# XInC2_Dev_-_SCH_v2_0_0_20210410.net
KiCad netlist of a schematic drawn in Altium Designer
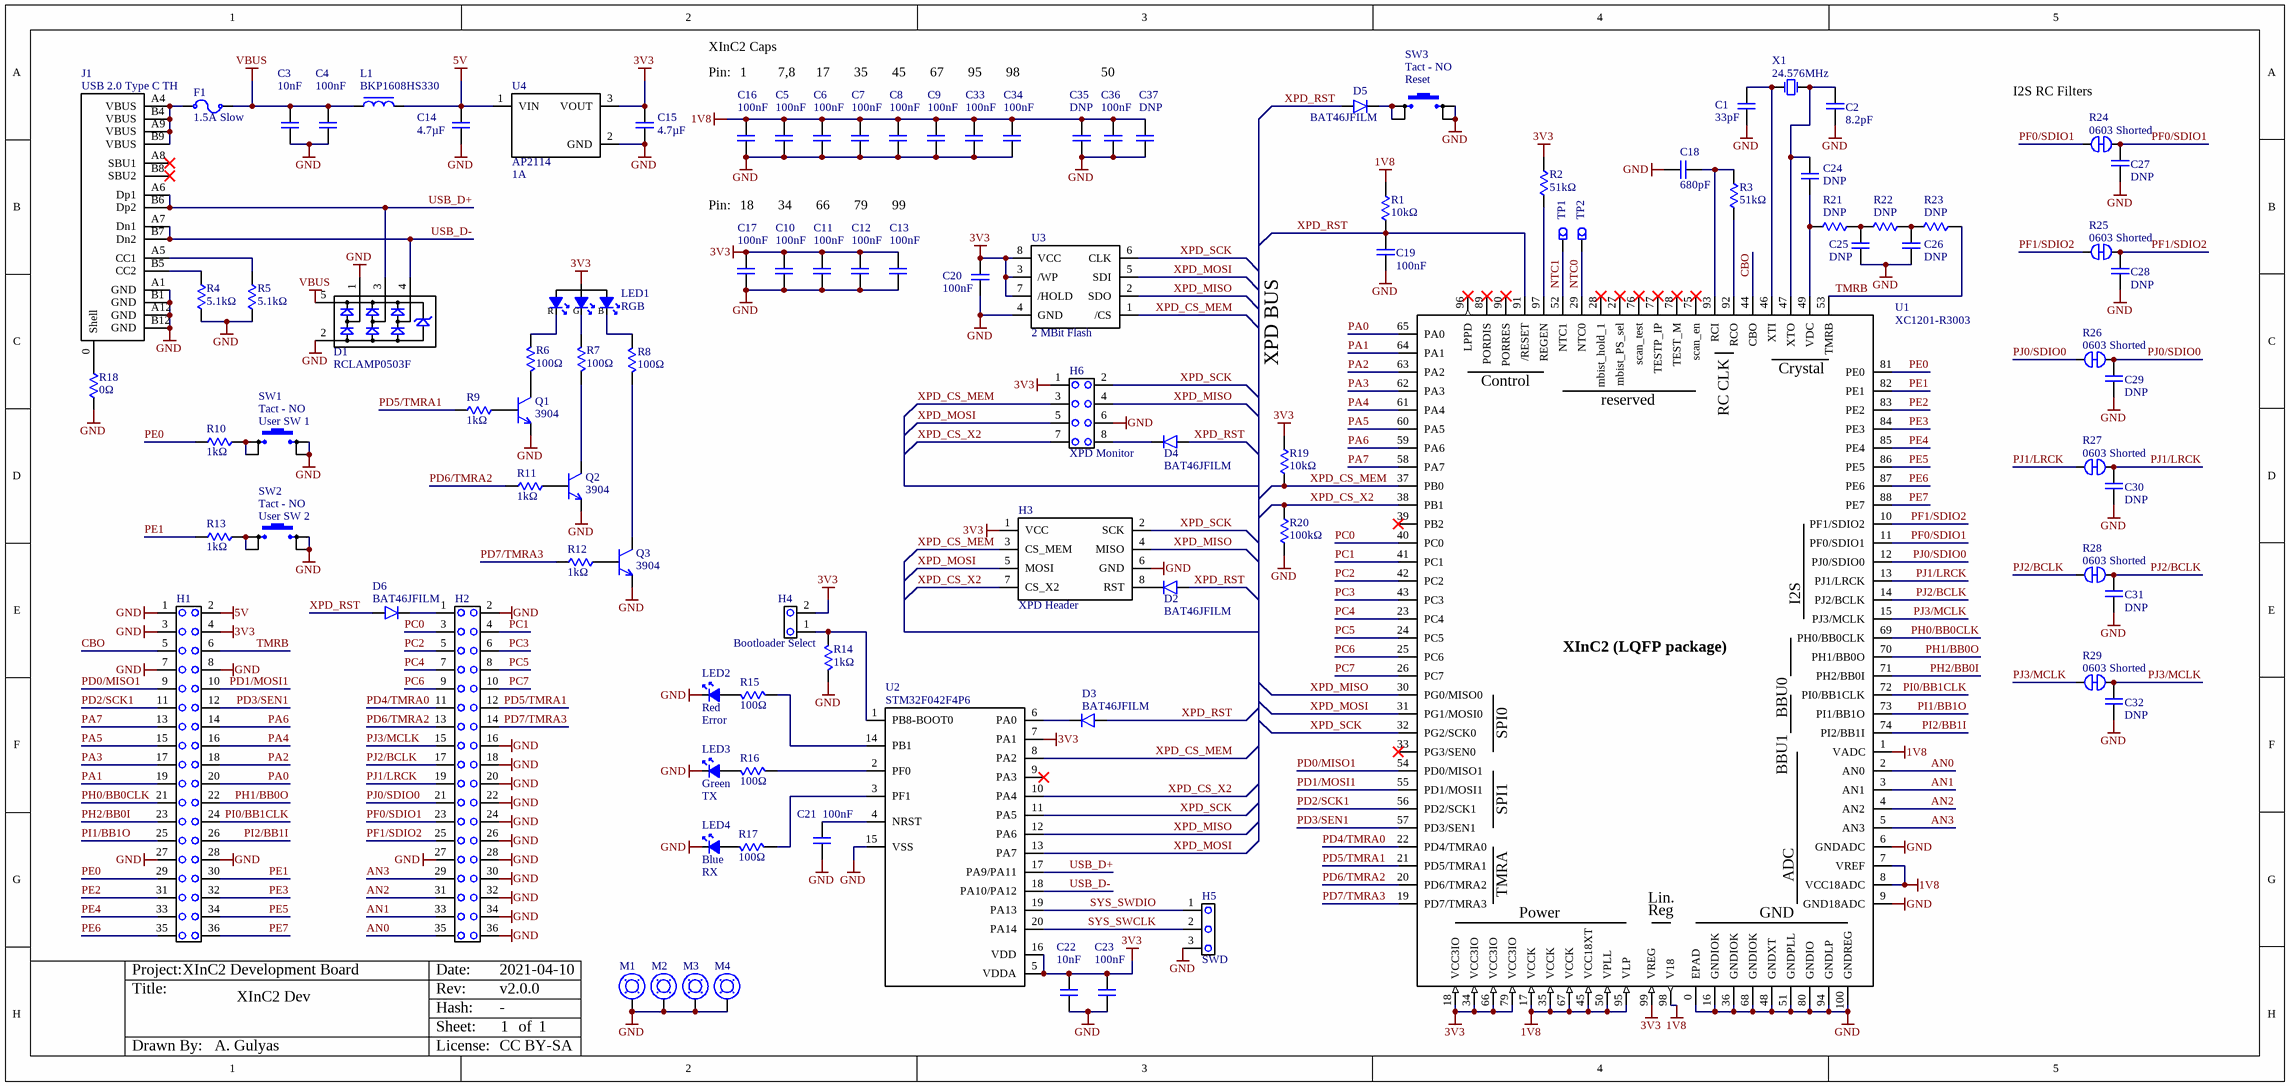
[diagram p0: XInC2 Dev - SCH v2.0.0 20210410.SchDoc]

(export (version "E")
  (design (tool "Eeschema 10.0.6"))
  (components
    (comp (ref "C1")
      (value "33pF")
      (footprint "0603 - C")
      (description "CAP CER 33PF 50V C0G/NPO 0603")
      (fields (field (name "MFG") "Yageo") (field (name "TOLERANCE") "±5%"))
      (libsource (lib "Public Library") (part "C - 0603 - 33pF - 16V_1"))
    )
    (comp (ref "C2")
      (value "8.2pF")
      (footprint "0603 - C")
      (description "CAP CER 8.2PF 50V NPO 0603")
      (fields (field (name "MFG") "Yageo") (field (name "TOLERANCE") "±0.25pF"))
      (libsource (lib "Public Library") (part "C - 0603 - 8.2pF - 50V"))
    )
    (comp (ref "C3")
      (value "10nF")
      (footprint "0603 - C")
      (description "CAP CER 10000PF 50V X7R 0603")
      (fields (field (name "MFG") "Yageo") (field (name "TOLERANCE") "±5%"))
      (libsource (lib "Public Library") (part "C - 0603 - 10nF - 50V"))
    )
    (comp (ref "C4")
      (value "100nF")
      (footprint "0603 - C")
      (description "CAP CER 0.1UF 16V X7R 0603")
      (fields (field (name "MFG") "Yageo") (field (name "TOLERANCE") "±10%"))
      (libsource (lib "Public Library") (part "C - 0603 - 100nF - 16V"))
    )
    (comp (ref "C5")
      (value "100nF")
      (footprint "0603 - C")
      (description "CAP CER 0.1UF 16V X7R 0603")
      (fields (field (name "MFG") "Yageo") (field (name "TOLERANCE") "±10%"))
      (libsource (lib "Public Library") (part "C - 0603 - 100nF - 16V"))
    )
    (comp (ref "C6")
      (value "100nF")
      (footprint "0603 - C")
      (description "CAP CER 0.1UF 16V X7R 0603")
      (fields (field (name "MFG") "Yageo") (field (name "TOLERANCE") "±10%"))
      (libsource (lib "Public Library") (part "C - 0603 - 100nF - 16V"))
    )
    (comp (ref "C7")
      (value "100nF")
      (footprint "0603 - C")
      (description "CAP CER 0.1UF 16V X7R 0603")
      (fields (field (name "MFG") "Yageo") (field (name "TOLERANCE") "±10%"))
      (libsource (lib "Public Library") (part "C - 0603 - 100nF - 16V"))
    )
    (comp (ref "C8")
      (value "100nF")
      (footprint "0603 - C")
      (description "CAP CER 0.1UF 16V X7R 0603")
      (fields (field (name "MFG") "Yageo") (field (name "TOLERANCE") "±10%"))
      (libsource (lib "Public Library") (part "C - 0603 - 100nF - 16V"))
    )
    (comp (ref "C9")
      (value "100nF")
      (footprint "0603 - C")
      (description "CAP CER 0.1UF 16V X7R 0603")
      (fields (field (name "MFG") "Yageo") (field (name "TOLERANCE") "±10%"))
      (libsource (lib "Public Library") (part "C - 0603 - 100nF - 16V"))
    )
    (comp (ref "C10")
      (value "100nF")
      (footprint "0603 - C")
      (description "CAP CER 0.1UF 16V X7R 0603")
      (fields (field (name "MFG") "Yageo") (field (name "TOLERANCE") "±10%"))
      (libsource (lib "Public Library") (part "C - 0603 - 100nF - 16V"))
    )
    (comp (ref "C11")
      (value "100nF")
      (footprint "0603 - C")
      (description "CAP CER 0.1UF 16V X7R 0603")
      (fields (field (name "MFG") "Yageo") (field (name "TOLERANCE") "±10%"))
      (libsource (lib "Public Library") (part "C - 0603 - 100nF - 16V"))
    )
    (comp (ref "C12")
      (value "100nF")
      (footprint "0603 - C")
      (description "CAP CER 0.1UF 16V X7R 0603")
      (fields (field (name "MFG") "Yageo") (field (name "TOLERANCE") "±10%"))
      (libsource (lib "Public Library") (part "C - 0603 - 100nF - 16V"))
    )
    (comp (ref "C13")
      (value "100nF")
      (footprint "0603 - C")
      (description "CAP CER 0.1UF 16V X7R 0603")
      (fields (field (name "MFG") "Yageo") (field (name "TOLERANCE") "±10%"))
      (libsource (lib "Public Library") (part "C - 0603 - 100nF - 16V"))
    )
    (comp (ref "C14")
      (value "4.7µF")
      (footprint "0603 - C")
      (description "CAP CER 4.7UF 10V X5R 0603")
      (fields (field (name "MFG") "Yageo") (field (name "TOLERANCE") "±20%"))
      (libsource (lib "Public Library") (part "C - 0603 - 4.7uF - 10V"))
    )
    (comp (ref "C15")
      (value "4.7µF")
      (footprint "0603 - C")
      (description "CAP CER 4.7UF 10V X5R 0603")
      (fields (field (name "MFG") "Yageo") (field (name "TOLERANCE") "±20%"))
      (libsource (lib "Public Library") (part "C - 0603 - 4.7uF - 10V"))
    )
    (comp (ref "C16")
      (value "100nF")
      (footprint "0603 - C")
      (description "CAP CER 0.1UF 16V X7R 0603")
      (fields (field (name "MFG") "Yageo") (field (name "TOLERANCE") "±10%"))
      (libsource (lib "Public Library") (part "C - 0603 - 100nF - 16V"))
    )
    (comp (ref "C17")
      (value "100nF")
      (footprint "0603 - C")
      (description "CAP CER 0.1UF 16V X7R 0603")
      (fields (field (name "MFG") "Yageo") (field (name "TOLERANCE") "±10%"))
      (libsource (lib "Public Library") (part "C - 0603 - 100nF - 16V"))
    )
    (comp (ref "C18")
      (value "680pF")
      (footprint "0603 - C")
      (description "CAP CER 680PF 50V X7R 0603")
      (fields (field (name "MFG") "Yageo") (field (name "TOLERANCE") "±10%"))
      (libsource (lib "Public Library") (part "C - 0603 - 680pF - 50V"))
    )
    (comp (ref "C19")
      (value "100nF")
      (footprint "0603 - C")
      (description "CAP CER 0.1UF 16V X7R 0603")
      (fields (field (name "MFG") "Yageo") (field (name "TOLERANCE") "±10%"))
      (libsource (lib "Public Library") (part "C - 0603 - 100nF - 16V"))
    )
    (comp (ref "C20")
      (value "100nF")
      (footprint "0603 - C")
      (description "CAP CER 0.1UF 16V X7R 0603")
      (fields (field (name "MFG") "Yageo") (field (name "TOLERANCE") "±10%"))
      (libsource (lib "Public Library") (part "C - 0603 - 100nF - 16V"))
    )
    (comp (ref "C21")
      (value "100nF")
      (footprint "0603 - C")
      (description "CAP CER 0.1UF 16V X7R 0603")
      (fields (field (name "MFG") "Yageo") (field (name "TOLERANCE") "±10%"))
      (libsource (lib "Public Library") (part "C - 0603 - 100nF - 16V"))
    )
    (comp (ref "C22")
      (value "10nF")
      (footprint "0603 - C")
      (description "CAP CER 10000PF 50V X7R 0603")
      (fields (field (name "MFG") "Yageo") (field (name "TOLERANCE") "±5%"))
      (libsource (lib "Public Library") (part "C - 0603 - 10nF - 50V"))
    )
    (comp (ref "C23")
      (value "100nF")
      (footprint "0603 - C")
      (description "CAP CER 0.1UF 16V X7R 0603")
      (fields (field (name "MFG") "Yageo") (field (name "TOLERANCE") "±10%"))
      (libsource (lib "Public Library") (part "C - 0603 - 100nF - 16V"))
    )
    (comp (ref "C24")
      (value "DNP")
      (footprint "0603 - C - DNP")
      (description "DNP C 0603")
      (libsource (lib "Public Library") (part "C - 0603 - DNP"))
    )
    (comp (ref "C25")
      (value "DNP")
      (footprint "0603 - C - DNP")
      (description "DNP C 0603")
      (libsource (lib "Public Library") (part "C - 0603 - DNP"))
    )
    (comp (ref "C26")
      (value "DNP")
      (footprint "0603 - C - DNP")
      (description "DNP C 0603")
      (libsource (lib "Public Library") (part "C - 0603 - DNP"))
    )
    (comp (ref "C27")
      (value "DNP")
      (footprint "0603 - C - DNP")
      (description "DNP C 0603")
      (libsource (lib "Public Library") (part "C - 0603 - DNP"))
    )
    (comp (ref "C28")
      (value "DNP")
      (footprint "0603 - C - DNP")
      (description "DNP C 0603")
      (libsource (lib "Public Library") (part "C - 0603 - DNP"))
    )
    (comp (ref "C29")
      (value "DNP")
      (footprint "0603 - C - DNP")
      (description "DNP C 0603")
      (libsource (lib "Public Library") (part "C - 0603 - DNP"))
    )
    (comp (ref "C30")
      (value "DNP")
      (footprint "0603 - C - DNP")
      (description "DNP C 0603")
      (libsource (lib "Public Library") (part "C - 0603 - DNP"))
    )
    (comp (ref "C31")
      (value "DNP")
      (footprint "0603 - C - DNP")
      (description "DNP C 0603")
      (libsource (lib "Public Library") (part "C - 0603 - DNP"))
    )
    (comp (ref "C32")
      (value "DNP")
      (footprint "0603 - C - DNP")
      (description "DNP C 0603")
      (libsource (lib "Public Library") (part "C - 0603 - DNP"))
    )
    (comp (ref "C33")
      (value "100nF")
      (footprint "0603 - C")
      (description "CAP CER 0.1UF 16V X7R 0603")
      (fields (field (name "MFG") "Yageo") (field (name "TOLERANCE") "±10%"))
      (libsource (lib "Public Library") (part "C - 0603 - 100nF - 16V"))
    )
    (comp (ref "C34")
      (value "100nF")
      (footprint "0603 - C")
      (description "CAP CER 0.1UF 16V X7R 0603")
      (fields (field (name "MFG") "Yageo") (field (name "TOLERANCE") "±10%"))
      (libsource (lib "Public Library") (part "C - 0603 - 100nF - 16V"))
    )
    (comp (ref "C35")
      (value "DNP")
      (footprint "0603 - C - DNP")
      (description "DNP C 0603")
      (libsource (lib "Public Library") (part "C - 0603 - DNP"))
    )
    (comp (ref "C36")
      (value "100nF")
      (footprint "0603 - C")
      (description "CAP CER 0.1UF 16V X7R 0603")
      (fields (field (name "MFG") "Yageo") (field (name "TOLERANCE") "±10%"))
      (libsource (lib "Public Library") (part "C - 0603 - 100nF - 16V"))
    )
    (comp (ref "C37")
      (value "DNP")
      (footprint "0603 - C - DNP")
      (description "DNP C 0603")
      (libsource (lib "Public Library") (part "C - 0603 - DNP"))
    )
    (comp (ref "D1")
      (value "RCLAMP0503F")
      (footprint "SOT 353")
      (description "TVS DIODE 5V 25V SC70-5")
      (fields (field (name "MFG") "Semtech Corp"))
      (libsource (lib "Public Library") (part "TVS - USB - RCLAMP0503F"))
    )
    (comp (ref "D2")
      (value "BAT46JFILM")
      (footprint "SOD 323")
      (description "DIODE SCHOTTKY 100V 150MA SOD323")
      (fields (field (name "MFG") "ST"))
      (libsource (lib "Public Library") (part "D - BAT46JFILM"))
    )
    (comp (ref "D3")
      (value "BAT46JFILM")
      (footprint "SOD 323")
      (description "DIODE SCHOTTKY 100V 150MA SOD323")
      (fields (field (name "MFG") "ST"))
      (libsource (lib "Public Library") (part "D - BAT46JFILM"))
    )
    (comp (ref "D4")
      (value "BAT46JFILM")
      (footprint "SOD 323 and 0603")
      (description "DIODE SCHOTTKY 100V 150MA SOD323")
      (fields (field (name "MFG") "ST"))
      (libsource (lib "Public Library") (part "D - BAT46JFILM"))
    )
    (comp (ref "D5")
      (value "BAT46JFILM")
      (footprint "SOD 323")
      (description "DIODE SCHOTTKY 100V 150MA SOD323")
      (fields (field (name "MFG") "ST"))
      (libsource (lib "Public Library") (part "D - BAT46JFILM"))
    )
    (comp (ref "D6")
      (value "BAT46JFILM")
      (footprint "SOD 323")
      (description "DIODE SCHOTTKY 100V 150MA SOD323")
      (fields (field (name "MFG") "ST"))
      (libsource (lib "Public Library") (part "D - BAT46JFILM"))
    )
    (comp (ref "F1")
      (value "1.5A Slow")
      (footprint "Fuse - C1T Series")
      (description "FUSE 1.5A 63VAC/DC SLOW 1206")
      (fields (field (name "MFG") "Bel Fuse Inc."))
      (libsource (lib "Public Library") (part "Fuse - 1.5A slow"))
    )
    (comp (ref "H1")
      (value "SSQ-118-03-T-D")
      (footprint "H - 100mil - 2x18 - Stack - bottom insert")
      (description "CONN RCPT 36POS 0.1 TIN PCB")
      (fields (field (name "MFG") "Samtec"))
      (libsource (lib "Public Library") (part "H - 100mil - Stack - 2x18"))
    )
    (comp (ref "H2")
      (value "SSQ-118-03-T-D")
      (footprint "H - 100mil - 2x18 - Stack - bottom insert")
      (description "CONN RCPT 36POS 0.1 TIN PCB")
      (fields (field (name "MFG") "Samtec"))
      (libsource (lib "Public Library") (part "H - 100mil - Stack - 2x18"))
    )
    (comp (ref "H3")
      (value "XPD Header")
      (footprint "H - XPD")
      (description "CONN HEADER SMD 8POS 1.27MM")
      (fields (field (name "MFG") "Samtec Inc."))
      (libsource (lib "Public Library") (part "H - XPD - SMT"))
    )
    (comp (ref "H4")
      (value "H - 100mil - M - TH - 1x2")
      (footprint "H - 100mil - 1x2 - TH")
      (description "CONN HEADER VERT 2POS 2.54MM")
      (fields (field (name "PURPOSE") "Bootloader Select"))
      (libsource (lib "Public Library") (part "H - 100mil - M - TH - 1x2"))
    )
    (comp (ref "H5")
      (value "H - 100mil - M - TH - 1x3")
      (footprint "H - 100mil - 1x3 - TH")
      (description "CONN HEADER VERT 3POS 2.54MM")
      (fields (field (name "PURPOSE") "SWD"))
      (libsource (lib "Public Library") (part "H - 100mil - M - TH - 1x3"))
    )
    (comp (ref "H6")
      (value "H - 100mil - M - TH - 2x4")
      (footprint "H - 100mil - 2x4 - TH - DNP")
      (fields (field (name "PURPOSE") "XPD Monitor"))
      (libsource (lib "Public Library") (part "H - 100mil - M - TH - 2x4"))
    )
    (comp (ref "J1")
      (value "USB 2.0 Type C TH")
      (footprint "Jack - USB C - 2.0 - TH")
      (description "CONN RCPT USB2.0 TYPEC 16POS")
      (fields (field (name "MFG") "GCT"))
      (libsource (lib "Public Library") (part "Jack - USB C - USB4085"))
    )
    (comp (ref "L1")
      (value "BKP1608HS330")
      (footprint "0603 - R")
      (description "FERRITE BEAD 33 OHM 0603 1LN")
      (fields (field (name "MFG") "Taiyo Yuden"))
      (libsource (lib "Public Library") (part "Ferrite - 0603 - 33 ohm"))
    )
    (comp (ref "LED1")
      (value "RGB")
      (footprint "LED - RGB - 0606")
      (description "LED RGB CLEAR 4SMD")
      (fields (field (name "MFG") "Everlight Electronics"))
      (libsource (lib "Public Library") (part "LED - RGB"))
    )
    (comp (ref "LED2")
      (value "Red")
      (footprint "LED - Red - 0603")
      (description "LED RED CLEAR CHIP SMD")
      (fields (field (name "MFG") "Lite-On Inc.") (field (name "PURPOSE") "Error"))
      (libsource (lib "Public Library") (part "LED - Red"))
    )
    (comp (ref "LED3")
      (value "Green")
      (footprint "LED - Green - 0603")
      (description "LED GREEN CLEAR CHIP SMD")
      (fields (field (name "MFG") "Lite-On Inc.") (field (name "PURPOSE") "TX"))
      (libsource (lib "Public Library") (part "LED - Green"))
    )
    (comp (ref "LED4")
      (value "Blue")
      (footprint "LED - Blue - 0603")
      (description "LED BLUE CLEAR CHIP SMD")
      (fields (field (name "MFG") "Lite-On Inc.") (field (name "PURPOSE") "RX"))
      (libsource (lib "Public Library") (part "LED - Blue"))
    )
    (comp (ref "M1")
      (value "Mech - Bolt Hole - M3")
      (footprint "Bolt Hole - M3")
      (libsource (lib "Public Library") (part "Mech - Bolt Hole - M3"))
    )
    (comp (ref "M2")
      (value "Mech - Bolt Hole - M3")
      (footprint "Bolt Hole - M3")
      (libsource (lib "Public Library") (part "Mech - Bolt Hole - M3"))
    )
    (comp (ref "M3")
      (value "Mech - Bolt Hole - M3")
      (footprint "Bolt Hole - M3")
      (libsource (lib "Public Library") (part "Mech - Bolt Hole - M3"))
    )
    (comp (ref "M4")
      (value "Mech - Bolt Hole - M3")
      (footprint "Bolt Hole - M3")
      (libsource (lib "Public Library") (part "Mech - Bolt Hole - M3"))
    )
    (comp (ref "Q1")
      (value "3904")
      (footprint "SOT 23 - NPN - MCC")
      (description "TRANS NPN 40V 0.2A SOT23")
      (fields (field (name "MFG") "Micro Commercial"))
      (libsource (lib "Public Library") (part "Q - NPN - MMBT3904"))
    )
    (comp (ref "Q2")
      (value "3904")
      (footprint "SOT 23 - NPN - MCC")
      (description "TRANS NPN 40V 0.2A SOT23")
      (fields (field (name "MFG") "Micro Commercial"))
      (libsource (lib "Public Library") (part "Q - NPN - MMBT3904"))
    )
    (comp (ref "Q3")
      (value "3904")
      (footprint "SOT 23 - NPN - MCC")
      (description "TRANS NPN 40V 0.2A SOT23")
      (fields (field (name "MFG") "Micro Commercial"))
      (libsource (lib "Public Library") (part "Q - NPN - MMBT3904"))
    )
    (comp (ref "R1")
      (value "10kΩ")
      (footprint "0603 - R")
      (description "RES SMD 10K OHM 5% 1/10W 0603")
      (fields (field (name "MFG") "Yageo") (field (name "POWER") "0.1W"))
      (libsource (lib "Public Library") (part "R - 0603 - 10k"))
    )
    (comp (ref "R2")
      (value "51kΩ")
      (footprint "0603 - R")
      (description "RES SMD 51K OHM 5% 1/10W 0603")
      (fields (field (name "MFG") "Yageo") (field (name "POWER") "0.1W"))
      (libsource (lib "Public Library") (part "R - 0603 - 51k"))
    )
    (comp (ref "R3")
      (value "51kΩ")
      (footprint "0603 - R")
      (description "RES SMD 51K OHM 5% 1/10W 0603")
      (fields (field (name "MFG") "Yageo") (field (name "POWER") "0.1W"))
      (libsource (lib "Public Library") (part "R - 0603 - 51k"))
    )
    (comp (ref "R4")
      (value "5.1kΩ")
      (footprint "0603 - R")
      (description "RES SMD 5.1K OHM 5% 1/10W 0603")
      (fields (field (name "MFG") "Yageo") (field (name "POWER") "0.1W"))
      (libsource (lib "Public Library") (part "R - 0603 - 5.1k"))
    )
    (comp (ref "R5")
      (value "5.1kΩ")
      (footprint "0603 - R")
      (description "RES SMD 5.1K OHM 5% 1/10W 0603")
      (fields (field (name "MFG") "Yageo") (field (name "POWER") "0.1W"))
      (libsource (lib "Public Library") (part "R - 0603 - 5.1k"))
    )
    (comp (ref "R6")
      (value "100Ω")
      (footprint "0603 - R")
      (description "RES SMD 100 OHM 5% 1/10W 0603")
      (fields (field (name "MFG") "Yageo") (field (name "POWER") "0.1W"))
      (libsource (lib "Public Library") (part "R - 0603 - 100R"))
    )
    (comp (ref "R7")
      (value "100Ω")
      (footprint "0603 - R")
      (description "RES SMD 100 OHM 5% 1/10W 0603")
      (fields (field (name "MFG") "Yageo") (field (name "POWER") "0.1W"))
      (libsource (lib "Public Library") (part "R - 0603 - 100R"))
    )
    (comp (ref "R8")
      (value "100Ω")
      (footprint "0603 - R")
      (description "RES SMD 100 OHM 5% 1/10W 0603")
      (fields (field (name "MFG") "Yageo") (field (name "POWER") "0.1W"))
      (libsource (lib "Public Library") (part "R - 0603 - 100R"))
    )
    (comp (ref "R9")
      (value "1kΩ")
      (footprint "0603 - R")
      (description "RES SMD 1K OHM 5% 1/10W 0603")
      (fields (field (name "MFG") "Yageo") (field (name "POWER") "0.1W"))
      (libsource (lib "Public Library") (part "R - 0603 - 1k"))
    )
    (comp (ref "R10")
      (value "1kΩ")
      (footprint "0603 - R")
      (description "RES SMD 1K OHM 5% 1/10W 0603")
      (fields (field (name "MFG") "Yageo") (field (name "POWER") "0.1W"))
      (libsource (lib "Public Library") (part "R - 0603 - 1k"))
    )
    (comp (ref "R11")
      (value "1kΩ")
      (footprint "0603 - R")
      (description "RES SMD 1K OHM 5% 1/10W 0603")
      (fields (field (name "MFG") "Yageo") (field (name "POWER") "0.1W"))
      (libsource (lib "Public Library") (part "R - 0603 - 1k"))
    )
    (comp (ref "R12")
      (value "1kΩ")
      (footprint "0603 - R")
      (description "RES SMD 1K OHM 5% 1/10W 0603")
      (fields (field (name "MFG") "Yageo") (field (name "POWER") "0.1W"))
      (libsource (lib "Public Library") (part "R - 0603 - 1k"))
    )
    (comp (ref "R13")
      (value "1kΩ")
      (footprint "0603 - R")
      (description "RES SMD 1K OHM 5% 1/10W 0603")
      (fields (field (name "MFG") "Yageo") (field (name "POWER") "0.1W"))
      (libsource (lib "Public Library") (part "R - 0603 - 1k"))
    )
    (comp (ref "R14")
      (value "1kΩ")
      (footprint "0603 - R")
      (description "RES SMD 1K OHM 5% 1/10W 0603")
      (fields (field (name "MFG") "Yageo") (field (name "POWER") "0.1W"))
      (libsource (lib "Public Library") (part "R - 0603 - 1k"))
    )
    (comp (ref "R15")
      (value "100Ω")
      (footprint "0603 - R")
      (description "RES SMD 100 OHM 5% 1/10W 0603")
      (fields (field (name "MFG") "Yageo") (field (name "POWER") "0.1W"))
      (libsource (lib "Public Library") (part "R - 0603 - 100R"))
    )
    (comp (ref "R16")
      (value "100Ω")
      (footprint "0603 - R")
      (description "RES SMD 100 OHM 5% 1/10W 0603")
      (fields (field (name "MFG") "Yageo") (field (name "POWER") "0.1W"))
      (libsource (lib "Public Library") (part "R - 0603 - 100R"))
    )
    (comp (ref "R17")
      (value "100Ω")
      (footprint "0603 - R")
      (description "RES SMD 100 OHM 5% 1/10W 0603")
      (fields (field (name "MFG") "Yageo") (field (name "POWER") "0.1W"))
      (libsource (lib "Public Library") (part "R - 0603 - 100R"))
    )
    (comp (ref "R18")
      (value "0Ω")
      (footprint "0603 - R")
      (description "RES SMD 0 OHM JUMPER 1/10W 0603")
      (fields (field (name "MFG") "Yageo") (field (name "POWER") "0.1W"))
      (libsource (lib "Public Library") (part "Jumper - 0603"))
    )
    (comp (ref "R19")
      (value "10kΩ")
      (footprint "0603 - R")
      (description "RES SMD 10K OHM 5% 1/10W 0603")
      (fields (field (name "MFG") "Yageo") (field (name "POWER") "0.1W"))
      (libsource (lib "Public Library") (part "R - 0603 - 10k"))
    )
    (comp (ref "R20")
      (value "100kΩ")
      (footprint "0603 - R")
      (description "RES SMD 100K OHM 5% 1/10W 0603")
      (fields (field (name "MFG") "Yageo") (field (name "POWER") "0.1W"))
      (libsource (lib "Public Library") (part "R - 0603 - 100k"))
    )
    (comp (ref "R21")
      (value "DNP")
      (footprint "0603 - R - DNP")
      (description "DNP R 0603")
      (libsource (lib "Public Library") (part "R - 0603 - DNP"))
    )
    (comp (ref "R22")
      (value "DNP")
      (footprint "0603 - R - DNP")
      (description "DNP R 0603")
      (libsource (lib "Public Library") (part "R - 0603 - DNP"))
    )
    (comp (ref "R23")
      (value "DNP")
      (footprint "0603 - R - DNP")
      (description "DNP R 0603")
      (libsource (lib "Public Library") (part "R - 0603 - DNP"))
    )
    (comp (ref "R24")
      (value "0603 Shorted")
      (footprint "0603 - R - shorted jumper")
      (description "DNP: 0603 Resistor with the pads shorted")
      (fields (field (name "MFG") "Yageo") (field (name "POWER") "0.1W"))
      (libsource (lib "Public Library") (part "Jumper - 0603 - Shorted"))
    )
    (comp (ref "R25")
      (value "0603 Shorted")
      (footprint "0603 - R - shorted jumper")
      (description "DNP: 0603 Resistor with the pads shorted")
      (fields (field (name "MFG") "Yageo") (field (name "POWER") "0.1W"))
      (libsource (lib "Public Library") (part "Jumper - 0603 - Shorted"))
    )
    (comp (ref "R26")
      (value "0603 Shorted")
      (footprint "0603 - R - shorted jumper")
      (description "DNP: 0603 Resistor with the pads shorted")
      (fields (field (name "MFG") "Yageo") (field (name "POWER") "0.1W"))
      (libsource (lib "Public Library") (part "Jumper - 0603 - Shorted"))
    )
    (comp (ref "R27")
      (value "0603 Shorted")
      (footprint "0603 - R - shorted jumper")
      (description "DNP: 0603 Resistor with the pads shorted")
      (fields (field (name "MFG") "Yageo") (field (name "POWER") "0.1W"))
      (libsource (lib "Public Library") (part "Jumper - 0603 - Shorted"))
    )
    (comp (ref "R28")
      (value "0603 Shorted")
      (footprint "0603 - R - shorted jumper")
      (description "DNP: 0603 Resistor with the pads shorted")
      (fields (field (name "MFG") "Yageo") (field (name "POWER") "0.1W"))
      (libsource (lib "Public Library") (part "Jumper - 0603 - Shorted"))
    )
    (comp (ref "R29")
      (value "0603 Shorted")
      (footprint "0603 - R - shorted jumper")
      (description "DNP: 0603 Resistor with the pads shorted")
      (fields (field (name "MFG") "Yageo") (field (name "POWER") "0.1W"))
      (libsource (lib "Public Library") (part "Jumper - 0603 - Shorted"))
    )
    (comp (ref "SW1")
      (value "Tact - NO")
      (footprint "SW - Tact - SMT")
      (description "SWITCH TACTILE SPST-NO 3VA 28V")
      (fields (field (name "PURPOSE") "User SW 1") (field (name "MFG") "NKK Switches"))
      (libsource (lib "Public Library") (part "SW - Tactile - HP0315AFKP2-R"))
    )
    (comp (ref "SW2")
      (value "Tact - NO")
      (footprint "SW - Tact - SMT")
      (description "SWITCH TACTILE SPST-NO 3VA 28V")
      (fields (field (name "PURPOSE") "User SW 2") (field (name "MFG") "NKK Switches"))
      (libsource (lib "Public Library") (part "SW - Tactile - HP0315AFKP2-R"))
    )
    (comp (ref "SW3")
      (value "Tact - NO")
      (footprint "SW - Tact - SMT")
      (description "SWITCH TACTILE SPST-NO 3VA 28V")
      (fields (field (name "PURPOSE") "Reset") (field (name "MFG") "NKK Switches"))
      (libsource (lib "Public Library") (part "SW - Tactile - HP0315AFKP2-R"))
    )
    (comp (ref "TP1")
      (value "Signal")
      (footprint "TP - TH - 0.6mm")
      (libsource (lib "Public Library") (part "TP - TH - 0.6 mm"))
    )
    (comp (ref "TP2")
      (value "Signal")
      (footprint "TP - TH - 0.6mm")
      (libsource (lib "Public Library") (part "TP - TH - 0.6 mm"))
    )
    (comp (ref "U1")
      (value "XC1201-R3003")
      (footprint "XInC2 LQFP 100")
      (description "XInC2 Multi-Threaded µC LQFP")
      (fields (field (name "MFG") "Eleven Engineering"))
      (libsource (lib "Public Library") (part "uC - XInC2 - LQFP"))
    )
    (comp (ref "U2")
      (value "STM32F042F4P6")
      (footprint "TSSOP 20")
      (description "IC MCU 32BIT 16KB FLASH 20TSSOP")
      (fields (field (name "MFG") "ST"))
      (libsource (lib "Public Library") (part "uC - STM32F042F4P6"))
    )
    (comp (ref "U3")
      (value "2 MBit Flash")
      (footprint "SOIC 8")
      (description "IC FLASH 2MBIT SPI 104MHZ 8SOIC")
      (fields (field (name "MFG") "Winbond Electronics"))
      (libsource (lib "Public Library") (part "Mem - Flash - 2 MBit - W25Q20CL"))
    )
    (comp (ref "U4")
      (value "AP2114")
      (footprint "SOT 223")
      (description "IC REG LINEAR 3.3V 1A SOT223")
      (fields (field (name "MFG") "Diodes Inc") (field (name "CURRENT - OUTPUT") "1A"))
      (libsource (lib "Public Library") (part "Reg - Lin - 3.3V - AP2114"))
    )
    (comp (ref "X1")
      (value "24.576MHz")
      (footprint "X - HC-49/US")
      (description "CRYSTAL 24.576MHZ SMD")
      (fields (field (name "MFG") "Huijing"))
      (libsource (lib "Public Library") (part "X - 20 MHz - HJ24.576"))
    )
  )
  (nets
    (net (code "1") (name "/AN0") (class "Default")
      (node (ref "H2") (pin "35") (pinfunction "35_35") (pintype "passive"))
      (node (ref "U1") (pin "2") (pinfunction "AN0_2") (pintype "passive"))
    )
    (net (code "2") (name "/AN1") (class "Default")
      (node (ref "H2") (pin "33") (pinfunction "33_33") (pintype "passive"))
      (node (ref "U1") (pin "3") (pinfunction "AN1_3") (pintype "passive"))
    )
    (net (code "3") (name "/AN2") (class "Default")
      (node (ref "H2") (pin "31") (pinfunction "31_31") (pintype "passive"))
      (node (ref "U1") (pin "4") (pinfunction "AN2_4") (pintype "passive"))
    )
    (net (code "4") (name "/AN3") (class "Default")
      (node (ref "H2") (pin "29") (pinfunction "29_29") (pintype "passive"))
      (node (ref "U1") (pin "5") (pinfunction "AN3_5") (pintype "passive"))
    )
    (net (code "5") (name "/CBO") (class "Default")
      (node (ref "H1") (pin "5") (pinfunction "5_5") (pintype "passive"))
      (node (ref "U1") (pin "44") (pinfunction "CBO_44") (pintype "passive"))
    )
    (net (code "6") (name "/NTC0") (class "Default")
      (node (ref "TP2") (pin "1") (pinfunction "1_1") (pintype "passive"))
      (node (ref "U1") (pin "29") (pinfunction "NTC0_29") (pintype "passive"))
    )
    (net (code "7") (name "/NTC1") (class "Default")
      (node (ref "TP1") (pin "1") (pinfunction "1_1") (pintype "passive"))
      (node (ref "U1") (pin "52") (pinfunction "NTC1_52") (pintype "passive"))
    )
    (net (code "8") (name "/PA0") (class "Default")
      (node (ref "H1") (pin "20") (pinfunction "20_20") (pintype "passive"))
      (node (ref "U1") (pin "65") (pinfunction "PA0_65") (pintype "passive"))
    )
    (net (code "9") (name "/PA1") (class "Default")
      (node (ref "H1") (pin "19") (pinfunction "19_19") (pintype "passive"))
      (node (ref "U1") (pin "64") (pinfunction "PA1_64") (pintype "passive"))
    )
    (net (code "10") (name "/PA2") (class "Default")
      (node (ref "H1") (pin "18") (pinfunction "18_18") (pintype "passive"))
      (node (ref "U1") (pin "63") (pinfunction "PA2_63") (pintype "passive"))
    )
    (net (code "11") (name "/PA3") (class "Default")
      (node (ref "H1") (pin "17") (pinfunction "17_17") (pintype "passive"))
      (node (ref "U1") (pin "62") (pinfunction "PA3_62") (pintype "passive"))
    )
    (net (code "12") (name "/PA4") (class "Default")
      (node (ref "H1") (pin "16") (pinfunction "16_16") (pintype "passive"))
      (node (ref "U1") (pin "61") (pinfunction "PA4_61") (pintype "passive"))
    )
    (net (code "13") (name "/PA5") (class "Default")
      (node (ref "H1") (pin "15") (pinfunction "15_15") (pintype "passive"))
      (node (ref "U1") (pin "60") (pinfunction "PA5_60") (pintype "passive"))
    )
    (net (code "14") (name "/PA6") (class "Default")
      (node (ref "H1") (pin "14") (pinfunction "14_14") (pintype "passive"))
      (node (ref "U1") (pin "59") (pinfunction "PA6_59") (pintype "passive"))
    )
    (net (code "15") (name "/PA7") (class "Default")
      (node (ref "H1") (pin "13") (pinfunction "13_13") (pintype "passive"))
      (node (ref "U1") (pin "58") (pinfunction "PA7_58") (pintype "passive"))
    )
    (net (code "16") (name "/PC0") (class "Default")
      (node (ref "H2") (pin "3") (pinfunction "3_3") (pintype "passive"))
      (node (ref "U1") (pin "40") (pinfunction "PC0_40") (pintype "passive"))
    )
    (net (code "17") (name "/PC1") (class "Default")
      (node (ref "H2") (pin "4") (pinfunction "4_4") (pintype "passive"))
      (node (ref "U1") (pin "41") (pinfunction "PC1_41") (pintype "passive"))
    )
    (net (code "18") (name "/PC2") (class "Default")
      (node (ref "H2") (pin "5") (pinfunction "5_5") (pintype "passive"))
      (node (ref "U1") (pin "42") (pinfunction "PC2_42") (pintype "passive"))
    )
    (net (code "19") (name "/PC3") (class "Default")
      (node (ref "H2") (pin "6") (pinfunction "6_6") (pintype "passive"))
      (node (ref "U1") (pin "43") (pinfunction "PC3_43") (pintype "passive"))
    )
    (net (code "20") (name "/PC4") (class "Default")
      (node (ref "H2") (pin "7") (pinfunction "7_7") (pintype "passive"))
      (node (ref "U1") (pin "23") (pinfunction "PC4_23") (pintype "passive"))
    )
    (net (code "21") (name "/PC5") (class "Default")
      (node (ref "H2") (pin "8") (pinfunction "8_8") (pintype "passive"))
      (node (ref "U1") (pin "24") (pinfunction "PC5_24") (pintype "passive"))
    )
    (net (code "22") (name "/PC6") (class "Default")
      (node (ref "H2") (pin "9") (pinfunction "9_9") (pintype "passive"))
      (node (ref "U1") (pin "25") (pinfunction "PC6_25") (pintype "passive"))
    )
    (net (code "23") (name "/PC7") (class "Default")
      (node (ref "H2") (pin "10") (pinfunction "10_10") (pintype "passive"))
      (node (ref "U1") (pin "26") (pinfunction "PC7_26") (pintype "passive"))
    )
    (net (code "24") (name "/PD0{slash}MISO1") (class "Default")
      (node (ref "H1") (pin "9") (pinfunction "9_9") (pintype "passive"))
      (node (ref "U1") (pin "54") (pinfunction "PD0/MISO1_54") (pintype "passive"))
    )
    (net (code "25") (name "/PD1{slash}MOSI1") (class "Default")
      (node (ref "H1") (pin "10") (pinfunction "10_10") (pintype "passive"))
      (node (ref "U1") (pin "55") (pinfunction "PD1/MOSI1_55") (pintype "passive"))
    )
    (net (code "26") (name "/PD2{slash}SCK1") (class "Default")
      (node (ref "H1") (pin "11") (pinfunction "11_11") (pintype "passive"))
      (node (ref "U1") (pin "56") (pinfunction "PD2/SCK1_56") (pintype "passive"))
    )
    (net (code "27") (name "/PD3{slash}SEN1") (class "Default")
      (node (ref "H1") (pin "12") (pinfunction "12_12") (pintype "passive"))
      (node (ref "U1") (pin "57") (pinfunction "PD3/SEN1_57") (pintype "passive"))
    )
    (net (code "28") (name "/PD4{slash}TMRA0") (class "Default")
      (node (ref "H2") (pin "11") (pinfunction "11_11") (pintype "passive"))
      (node (ref "U1") (pin "22") (pinfunction "PD4/TMRA0_22") (pintype "passive"))
    )
    (net (code "29") (name "/PD5{slash}TMRA1") (class "Default")
      (node (ref "H2") (pin "12") (pinfunction "12_12") (pintype "passive"))
      (node (ref "R9") (pin "1") (pinfunction "1_1") (pintype "passive"))
      (node (ref "U1") (pin "21") (pinfunction "PD5/TMRA1_21") (pintype "passive"))
    )
    (net (code "30") (name "/PD6{slash}TMRA2") (class "Default")
      (node (ref "H2") (pin "13") (pinfunction "13_13") (pintype "passive"))
      (node (ref "R11") (pin "1") (pinfunction "1_1") (pintype "passive"))
      (node (ref "U1") (pin "20") (pinfunction "PD6/TMRA2_20") (pintype "passive"))
    )
    (net (code "31") (name "/PD7{slash}TMRA3") (class "Default")
      (node (ref "H2") (pin "14") (pinfunction "14_14") (pintype "passive"))
      (node (ref "R12") (pin "1") (pinfunction "1_1") (pintype "passive"))
      (node (ref "U1") (pin "19") (pinfunction "PD7/TMRA3_19") (pintype "passive"))
    )
    (net (code "32") (name "/PE0") (class "Default")
      (node (ref "H1") (pin "29") (pinfunction "29_29") (pintype "passive"))
      (node (ref "R10") (pin "1") (pinfunction "1_1") (pintype "passive"))
      (node (ref "U1") (pin "81") (pinfunction "PE0_81") (pintype "passive"))
    )
    (net (code "33") (name "/PE1") (class "Default")
      (node (ref "H1") (pin "30") (pinfunction "30_30") (pintype "passive"))
      (node (ref "R13") (pin "1") (pinfunction "1_1") (pintype "passive"))
      (node (ref "U1") (pin "82") (pinfunction "PE1_82") (pintype "passive"))
    )
    (net (code "34") (name "/PE2") (class "Default")
      (node (ref "H1") (pin "31") (pinfunction "31_31") (pintype "passive"))
      (node (ref "U1") (pin "83") (pinfunction "PE2_83") (pintype "passive"))
    )
    (net (code "35") (name "/PE3") (class "Default")
      (node (ref "H1") (pin "32") (pinfunction "32_32") (pintype "passive"))
      (node (ref "U1") (pin "84") (pinfunction "PE3_84") (pintype "passive"))
    )
    (net (code "36") (name "/PE4") (class "Default")
      (node (ref "H1") (pin "33") (pinfunction "33_33") (pintype "passive"))
      (node (ref "U1") (pin "85") (pinfunction "PE4_85") (pintype "passive"))
    )
    (net (code "37") (name "/PE5") (class "Default")
      (node (ref "H1") (pin "34") (pinfunction "34_34") (pintype "passive"))
      (node (ref "U1") (pin "86") (pinfunction "PE5_86") (pintype "passive"))
    )
    (net (code "38") (name "/PE6") (class "Default")
      (node (ref "H1") (pin "35") (pinfunction "35_35") (pintype "passive"))
      (node (ref "U1") (pin "87") (pinfunction "PE6_87") (pintype "passive"))
    )
    (net (code "39") (name "/PE7") (class "Default")
      (node (ref "H1") (pin "36") (pinfunction "36_36") (pintype "passive"))
      (node (ref "U1") (pin "88") (pinfunction "PE7_88") (pintype "passive"))
    )
    (net (code "40") (name "/PF0{slash}SDIO1") (class "Default")
      (node (ref "C27") (pin "1") (pinfunction "1_1") (pintype "passive"))
      (node (ref "H2") (pin "23") (pinfunction "23_23") (pintype "passive"))
      (node (ref "R24") (pin "1") (pinfunction "1_1") (pintype "passive"))
      (node (ref "R24") (pin "2") (pinfunction "2_2") (pintype "passive"))
      (node (ref "U1") (pin "11") (pinfunction "PF0/SDIO1_11") (pintype "passive"))
    )
    (net (code "41") (name "/PF1{slash}SDIO2") (class "Default")
      (node (ref "C28") (pin "1") (pinfunction "1_1") (pintype "passive"))
      (node (ref "H2") (pin "25") (pinfunction "25_25") (pintype "passive"))
      (node (ref "R25") (pin "1") (pinfunction "1_1") (pintype "passive"))
      (node (ref "R25") (pin "2") (pinfunction "2_2") (pintype "passive"))
      (node (ref "U1") (pin "10") (pinfunction "PF1/SDIO2_10") (pintype "passive"))
    )
    (net (code "42") (name "/PH0{slash}BB0CLK") (class "Default")
      (node (ref "H1") (pin "21") (pinfunction "21_21") (pintype "passive"))
      (node (ref "U1") (pin "69") (pinfunction "PH0/BB0CLK_69") (pintype "passive"))
    )
    (net (code "43") (name "/PH1{slash}BB0O") (class "Default")
      (node (ref "H1") (pin "22") (pinfunction "22_22") (pintype "passive"))
      (node (ref "U1") (pin "70") (pinfunction "PH1/BB0O_70") (pintype "passive"))
    )
    (net (code "44") (name "/PH2{slash}BB0I") (class "Default")
      (node (ref "H1") (pin "23") (pinfunction "23_23") (pintype "passive"))
      (node (ref "U1") (pin "71") (pinfunction "PH2/BB0I_71") (pintype "passive"))
    )
    (net (code "45") (name "/PI0{slash}BB1CLK") (class "Default")
      (node (ref "H1") (pin "24") (pinfunction "24_24") (pintype "passive"))
      (node (ref "U1") (pin "72") (pinfunction "PI0/BB1CLK_72") (pintype "passive"))
    )
    (net (code "46") (name "/PI1{slash}BB1O") (class "Default")
      (node (ref "H1") (pin "25") (pinfunction "25_25") (pintype "passive"))
      (node (ref "U1") (pin "73") (pinfunction "PI1/BB1O_73") (pintype "passive"))
    )
    (net (code "47") (name "/PI2{slash}BB1I") (class "Default")
      (node (ref "H1") (pin "26") (pinfunction "26_26") (pintype "passive"))
      (node (ref "U1") (pin "74") (pinfunction "PI2/BB1I_74") (pintype "passive"))
    )
    (net (code "48") (name "/PJ0{slash}SDIO0") (class "Default")
      (node (ref "C29") (pin "1") (pinfunction "1_1") (pintype "passive"))
      (node (ref "H2") (pin "21") (pinfunction "21_21") (pintype "passive"))
      (node (ref "R26") (pin "1") (pinfunction "1_1") (pintype "passive"))
      (node (ref "R26") (pin "2") (pinfunction "2_2") (pintype "passive"))
      (node (ref "U1") (pin "12") (pinfunction "PJ0/SDIO0_12") (pintype "passive"))
    )
    (net (code "49") (name "/PJ1{slash}LRCK") (class "Default")
      (node (ref "C30") (pin "1") (pinfunction "1_1") (pintype "passive"))
      (node (ref "H2") (pin "19") (pinfunction "19_19") (pintype "passive"))
      (node (ref "R27") (pin "1") (pinfunction "1_1") (pintype "passive"))
      (node (ref "R27") (pin "2") (pinfunction "2_2") (pintype "passive"))
      (node (ref "U1") (pin "13") (pinfunction "PJ1/LRCK_13") (pintype "passive"))
    )
    (net (code "50") (name "/PJ2{slash}BCLK") (class "Default")
      (node (ref "C31") (pin "1") (pinfunction "1_1") (pintype "passive"))
      (node (ref "H2") (pin "17") (pinfunction "17_17") (pintype "passive"))
      (node (ref "R28") (pin "1") (pinfunction "1_1") (pintype "passive"))
      (node (ref "R28") (pin "2") (pinfunction "2_2") (pintype "passive"))
      (node (ref "U1") (pin "14") (pinfunction "PJ2/BCLK_14") (pintype "passive"))
    )
    (net (code "51") (name "/PJ3{slash}MCLK") (class "Default")
      (node (ref "C32") (pin "1") (pinfunction "1_1") (pintype "passive"))
      (node (ref "H2") (pin "15") (pinfunction "15_15") (pintype "passive"))
      (node (ref "R29") (pin "1") (pinfunction "1_1") (pintype "passive"))
      (node (ref "R29") (pin "2") (pinfunction "2_2") (pintype "passive"))
      (node (ref "U1") (pin "15") (pinfunction "PJ3/MCLK_15") (pintype "passive"))
    )
    (net (code "52") (name "/SYS_SWCLK") (class "Default")
      (node (ref "H5") (pin "2") (pinfunction "2_2") (pintype "passive"))
      (node (ref "U2") (pin "20") (pinfunction "PA14_20") (pintype "passive"))
    )
    (net (code "53") (name "/SYS_SWDIO") (class "Default")
      (node (ref "H5") (pin "1") (pinfunction "1_1") (pintype "passive"))
      (node (ref "U2") (pin "19") (pinfunction "PA13_19") (pintype "passive"))
    )
    (net (code "54") (name "/TMRB") (class "Default")
      (node (ref "H1") (pin "6") (pinfunction "6_6") (pintype "passive"))
      (node (ref "R23") (pin "2") (pinfunction "2_2") (pintype "passive"))
      (node (ref "U1") (pin "53") (pinfunction "TMRB_53") (pintype "passive"))
    )
    (net (code "55") (name "/USB_D+") (class "Default")
      (node (ref "D1") (pin "3") (pinfunction "3_3") (pintype "passive"))
      (node (ref "J1") (pin "A6") (pinfunction "Dp1_A6") (pintype "passive"))
      (node (ref "J1") (pin "B6") (pinfunction "Dp2_B6") (pintype "passive"))
      (node (ref "U2") (pin "17") (pinfunction "PA9/PA11_17") (pintype "passive"))
    )
    (net (code "56") (name "/USB_D-") (class "Default")
      (node (ref "D1") (pin "4") (pinfunction "4_4") (pintype "passive"))
      (node (ref "J1") (pin "A7") (pinfunction "Dn1_A7") (pintype "passive"))
      (node (ref "J1") (pin "B7") (pinfunction "Dn2_B7") (pintype "passive"))
      (node (ref "U2") (pin "18") (pinfunction "PA10/PA12_18") (pintype "passive"))
    )
    (net (code "57") (name "/XPD_CS_MEM") (class "Default")
      (node (ref "H3") (pin "3") (pinfunction "CS_MEM_3") (pintype "passive"))
      (node (ref "H6") (pin "3") (pinfunction "3_3") (pintype "passive"))
      (node (ref "R19") (pin "1") (pinfunction "1_1") (pintype "passive"))
      (node (ref "U1") (pin "37") (pinfunction "PB0_37") (pintype "passive"))
      (node (ref "U2") (pin "8") (pinfunction "PA2_8") (pintype "passive"))
      (node (ref "U3") (pin "1") (pinfunction "/CS_1") (pintype "passive"))
    )
    (net (code "58") (name "/XPD_CS_X2") (class "Default")
      (node (ref "H3") (pin "7") (pinfunction "CS_X2_7") (pintype "passive"))
      (node (ref "H6") (pin "7") (pinfunction "7_7") (pintype "passive"))
      (node (ref "R20") (pin "2") (pinfunction "2_2") (pintype "passive"))
      (node (ref "U1") (pin "38") (pinfunction "PB1_38") (pintype "passive"))
      (node (ref "U2") (pin "10") (pinfunction "PA4_10") (pintype "passive"))
    )
    (net (code "59") (name "/XPD_MISO") (class "Default")
      (node (ref "H3") (pin "4") (pinfunction "MISO_4") (pintype "passive"))
      (node (ref "H6") (pin "4") (pinfunction "4_4") (pintype "passive"))
      (node (ref "U1") (pin "30") (pinfunction "PG0/MISO0_30") (pintype "passive"))
      (node (ref "U2") (pin "12") (pinfunction "PA6_12") (pintype "passive"))
      (node (ref "U3") (pin "2") (pinfunction "SDO_2") (pintype "passive"))
    )
    (net (code "60") (name "/XPD_MOSI") (class "Default")
      (node (ref "H3") (pin "5") (pinfunction "MOSI_5") (pintype "passive"))
      (node (ref "H6") (pin "5") (pinfunction "5_5") (pintype "passive"))
      (node (ref "U1") (pin "31") (pinfunction "PG1/MOSI0_31") (pintype "passive"))
      (node (ref "U2") (pin "13") (pinfunction "PA7_13") (pintype "passive"))
      (node (ref "U3") (pin "5") (pinfunction "SDI_5") (pintype "passive"))
    )
    (net (code "61") (name "/XPD_RST") (class "Default")
      (node (ref "C19") (pin "1") (pinfunction "1_1") (pintype "passive"))
      (node (ref "D2") (pin "1") (pinfunction "1_1") (pintype "passive"))
      (node (ref "D3") (pin "1") (pinfunction "1_1") (pintype "passive"))
      (node (ref "D4") (pin "1") (pinfunction "1_1") (pintype "passive"))
      (node (ref "D5") (pin "1") (pinfunction "1_1") (pintype "passive"))
      (node (ref "D6") (pin "1") (pinfunction "1_1") (pintype "passive"))
      (node (ref "R1") (pin "1") (pinfunction "1_1") (pintype "passive"))
      (node (ref "U1") (pin "91") (pinfunction "/RESET_91") (pintype "passive"))
    )
    (net (code "62") (name "/XPD_SCK") (class "Default")
      (node (ref "H3") (pin "2") (pinfunction "SCK_2") (pintype "passive"))
      (node (ref "H6") (pin "2") (pinfunction "2_2") (pintype "passive"))
      (node (ref "U1") (pin "32") (pinfunction "PG2/SCK0_32") (pintype "passive"))
      (node (ref "U2") (pin "11") (pinfunction "PA5_11") (pintype "passive"))
      (node (ref "U3") (pin "6") (pinfunction "CLK_6") (pintype "passive"))
    )
    (net (code "63") (name "1V8") (class "Default")
      (node (ref "C16") (pin "1") (pinfunction "1_1") (pintype "passive"))
      (node (ref "C33") (pin "1") (pinfunction "1_1") (pintype "passive"))
      (node (ref "C34") (pin "1") (pinfunction "1_1") (pintype "passive"))
      (node (ref "C35") (pin "1") (pinfunction "1_1") (pintype "passive"))
      (node (ref "C36") (pin "1") (pinfunction "1_1") (pintype "passive"))
      (node (ref "C37") (pin "1") (pinfunction "1_1") (pintype "passive"))
      (node (ref "C5") (pin "1") (pinfunction "1_1") (pintype "passive"))
      (node (ref "C6") (pin "1") (pinfunction "1_1") (pintype "passive"))
      (node (ref "C7") (pin "1") (pinfunction "1_1") (pintype "passive"))
      (node (ref "C8") (pin "1") (pinfunction "1_1") (pintype "passive"))
      (node (ref "C9") (pin "1") (pinfunction "1_1") (pintype "passive"))
      (node (ref "R1") (pin "2") (pinfunction "2_2") (pintype "passive"))
      (node (ref "U1") (pin "1") (pinfunction "VADC_1") (pintype "passive"))
      (node (ref "U1") (pin "17") (pinfunction "VCCK_17") (pintype "input"))
      (node (ref "U1") (pin "35") (pinfunction "VCCK_35") (pintype "input"))
      (node (ref "U1") (pin "45") (pinfunction "VCC18XT_45") (pintype "input"))
      (node (ref "U1") (pin "50") (pinfunction "VPLL_50") (pintype "input"))
      (node (ref "U1") (pin "67") (pinfunction "VCCK_67") (pintype "input"))
      (node (ref "U1") (pin "7") (pinfunction "VREF_7") (pintype "passive"))
      (node (ref "U1") (pin "8") (pinfunction "VCC18ADC_8") (pintype "passive"))
      (node (ref "U1") (pin "95") (pinfunction "VLP_95") (pintype "input"))
      (node (ref "U1") (pin "98") (pinfunction "V18_98") (pintype "output"))
    )
    (net (code "64") (name "3V3") (class "Default")
      (node (ref "C10") (pin "1") (pinfunction "1_1") (pintype "passive"))
      (node (ref "C11") (pin "1") (pinfunction "1_1") (pintype "passive"))
      (node (ref "C12") (pin "1") (pinfunction "1_1") (pintype "passive"))
      (node (ref "C13") (pin "1") (pinfunction "1_1") (pintype "passive"))
      (node (ref "C15") (pin "1") (pinfunction "1_1") (pintype "passive"))
      (node (ref "C17") (pin "1") (pinfunction "1_1") (pintype "passive"))
      (node (ref "C20") (pin "1") (pinfunction "1_1") (pintype "passive"))
      (node (ref "C22") (pin "1") (pinfunction "1_1") (pintype "passive"))
      (node (ref "C23") (pin "1") (pinfunction "1_1") (pintype "passive"))
      (node (ref "H1") (pin "4") (pinfunction "4_4") (pintype "passive"))
      (node (ref "H3") (pin "1") (pinfunction "VCC_1") (pintype "passive"))
      (node (ref "H4") (pin "2") (pinfunction "2_2") (pintype "passive"))
      (node (ref "H6") (pin "1") (pinfunction "1_1") (pintype "passive"))
      (node (ref "LED1") (pin "4") (pinfunction "4_4") (pintype "passive"))
      (node (ref "R19") (pin "2") (pinfunction "2_2") (pintype "passive"))
      (node (ref "R2") (pin "2") (pinfunction "2_2") (pintype "passive"))
      (node (ref "U1") (pin "18") (pinfunction "VCC3IO_18") (pintype "input"))
      (node (ref "U1") (pin "34") (pinfunction "VCC3IO_34") (pintype "input"))
      (node (ref "U1") (pin "66") (pinfunction "VCC3IO_66") (pintype "input"))
      (node (ref "U1") (pin "79") (pinfunction "VCC3IO_79") (pintype "input"))
      (node (ref "U1") (pin "99") (pinfunction "VREG_99") (pintype "input"))
      (node (ref "U2") (pin "16") (pinfunction "VDD_16") (pintype "passive"))
      (node (ref "U2") (pin "5") (pinfunction "VDDA_5") (pintype "passive"))
      (node (ref "U2") (pin "7") (pinfunction "PA1_7") (pintype "passive"))
      (node (ref "U3") (pin "3") (pinfunction "/WP_3") (pintype "passive"))
      (node (ref "U3") (pin "7") (pinfunction "/HOLD_7") (pintype "passive"))
      (node (ref "U3") (pin "8") (pinfunction "VCC_8") (pintype "passive"))
      (node (ref "U4") (pin "3") (pinfunction "VOUT_3") (pintype "passive"))
    )
    (net (code "65") (name "5V") (class "Default")
      (node (ref "C14") (pin "1") (pinfunction "1_1") (pintype "passive"))
      (node (ref "H1") (pin "2") (pinfunction "2_2") (pintype "passive"))
      (node (ref "L1") (pin "2") (pinfunction "2_2") (pintype "passive"))
      (node (ref "U4") (pin "1") (pinfunction "VIN_1") (pintype "passive"))
    )
    (net (code "66") (name "GND") (class "Default")
      (node (ref "C1") (pin "2") (pinfunction "2_2") (pintype "passive"))
      (node (ref "C10") (pin "2") (pinfunction "2_2") (pintype "passive"))
      (node (ref "C11") (pin "2") (pinfunction "2_2") (pintype "passive"))
      (node (ref "C12") (pin "2") (pinfunction "2_2") (pintype "passive"))
      (node (ref "C13") (pin "2") (pinfunction "2_2") (pintype "passive"))
      (node (ref "C14") (pin "2") (pinfunction "2_2") (pintype "passive"))
      (node (ref "C15") (pin "2") (pinfunction "2_2") (pintype "passive"))
      (node (ref "C16") (pin "2") (pinfunction "2_2") (pintype "passive"))
      (node (ref "C17") (pin "2") (pinfunction "2_2") (pintype "passive"))
      (node (ref "C18") (pin "1") (pinfunction "1_1") (pintype "passive"))
      (node (ref "C19") (pin "2") (pinfunction "2_2") (pintype "passive"))
      (node (ref "C2") (pin "2") (pinfunction "2_2") (pintype "passive"))
      (node (ref "C20") (pin "2") (pinfunction "2_2") (pintype "passive"))
      (node (ref "C21") (pin "2") (pinfunction "2_2") (pintype "passive"))
      (node (ref "C22") (pin "2") (pinfunction "2_2") (pintype "passive"))
      (node (ref "C23") (pin "2") (pinfunction "2_2") (pintype "passive"))
      (node (ref "C25") (pin "2") (pinfunction "2_2") (pintype "passive"))
      (node (ref "C26") (pin "2") (pinfunction "2_2") (pintype "passive"))
      (node (ref "C27") (pin "2") (pinfunction "2_2") (pintype "passive"))
      (node (ref "C28") (pin "2") (pinfunction "2_2") (pintype "passive"))
      (node (ref "C29") (pin "2") (pinfunction "2_2") (pintype "passive"))
      (node (ref "C3") (pin "2") (pinfunction "2_2") (pintype "passive"))
      (node (ref "C30") (pin "2") (pinfunction "2_2") (pintype "passive"))
      (node (ref "C31") (pin "2") (pinfunction "2_2") (pintype "passive"))
      (node (ref "C32") (pin "2") (pinfunction "2_2") (pintype "passive"))
      (node (ref "C33") (pin "2") (pinfunction "2_2") (pintype "passive"))
      (node (ref "C34") (pin "2") (pinfunction "2_2") (pintype "passive"))
      (node (ref "C35") (pin "2") (pinfunction "2_2") (pintype "passive"))
      (node (ref "C36") (pin "2") (pinfunction "2_2") (pintype "passive"))
      (node (ref "C37") (pin "2") (pinfunction "2_2") (pintype "passive"))
      (node (ref "C4") (pin "2") (pinfunction "2_2") (pintype "passive"))
      (node (ref "C5") (pin "2") (pinfunction "2_2") (pintype "passive"))
      (node (ref "C6") (pin "2") (pinfunction "2_2") (pintype "passive"))
      (node (ref "C7") (pin "2") (pinfunction "2_2") (pintype "passive"))
      (node (ref "C8") (pin "2") (pinfunction "2_2") (pintype "passive"))
      (node (ref "C9") (pin "2") (pinfunction "2_2") (pintype "passive"))
      (node (ref "D1") (pin "1") (pinfunction "1_1") (pintype "passive"))
      (node (ref "D1") (pin "2") (pinfunction "2_2") (pintype "passive"))
      (node (ref "H1") (pin "1") (pinfunction "1_1") (pintype "passive"))
      (node (ref "H1") (pin "27") (pinfunction "27_27") (pintype "passive"))
      (node (ref "H1") (pin "28") (pinfunction "28_28") (pintype "passive"))
      (node (ref "H1") (pin "3") (pinfunction "3_3") (pintype "passive"))
      (node (ref "H1") (pin "7") (pinfunction "7_7") (pintype "passive"))
      (node (ref "H1") (pin "8") (pinfunction "8_8") (pintype "passive"))
      (node (ref "H2") (pin "16") (pinfunction "16_16") (pintype "passive"))
      (node (ref "H2") (pin "18") (pinfunction "18_18") (pintype "passive"))
      (node (ref "H2") (pin "2") (pinfunction "2_2") (pintype "passive"))
      (node (ref "H2") (pin "20") (pinfunction "20_20") (pintype "passive"))
      (node (ref "H2") (pin "22") (pinfunction "22_22") (pintype "passive"))
      (node (ref "H2") (pin "24") (pinfunction "24_24") (pintype "passive"))
      (node (ref "H2") (pin "26") (pinfunction "26_26") (pintype "passive"))
      (node (ref "H2") (pin "27") (pinfunction "27_27") (pintype "passive"))
      (node (ref "H2") (pin "28") (pinfunction "28_28") (pintype "passive"))
      (node (ref "H2") (pin "30") (pinfunction "30_30") (pintype "passive"))
      (node (ref "H2") (pin "32") (pinfunction "32_32") (pintype "passive"))
      (node (ref "H2") (pin "34") (pinfunction "34_34") (pintype "passive"))
      (node (ref "H2") (pin "36") (pinfunction "36_36") (pintype "passive"))
      (node (ref "H3") (pin "6") (pinfunction "GND_6") (pintype "passive"))
      (node (ref "H5") (pin "3") (pinfunction "3_3") (pintype "passive"))
      (node (ref "H6") (pin "6") (pinfunction "6_6") (pintype "passive"))
      (node (ref "J1") (pin "A1") (pinfunction "GND_A1") (pintype "passive"))
      (node (ref "J1") (pin "A12") (pinfunction "GND_A12") (pintype "passive"))
      (node (ref "J1") (pin "B1") (pinfunction "GND_B1") (pintype "passive"))
      (node (ref "J1") (pin "B12") (pinfunction "GND_B12") (pintype "passive"))
      (node (ref "LED2") (pin "2") (pinfunction "2_2") (pintype "passive"))
      (node (ref "LED3") (pin "2") (pinfunction "2_2") (pintype "passive"))
      (node (ref "LED4") (pin "2") (pinfunction "2_2") (pintype "passive"))
      (node (ref "M1") (pin "1") (pinfunction "1_1") (pintype "passive"))
      (node (ref "M2") (pin "1") (pinfunction "1_1") (pintype "passive"))
      (node (ref "M3") (pin "1") (pinfunction "1_1") (pintype "passive"))
      (node (ref "M4") (pin "1") (pinfunction "1_1") (pintype "passive"))
      (node (ref "Q1") (pin "E") (pinfunction "E_E") (pintype "passive"))
      (node (ref "Q2") (pin "E") (pinfunction "E_E") (pintype "passive"))
      (node (ref "Q3") (pin "E") (pinfunction "E_E") (pintype "passive"))
      (node (ref "R14") (pin "1") (pinfunction "1_1") (pintype "passive"))
      (node (ref "R18") (pin "1") (pinfunction "1_1") (pintype "passive"))
      (node (ref "R20") (pin "1") (pinfunction "1_1") (pintype "passive"))
      (node (ref "R4") (pin "1") (pinfunction "1_1") (pintype "passive"))
      (node (ref "R5") (pin "1") (pinfunction "1_1") (pintype "passive"))
      (node (ref "SW1") (pin "1") (pinfunction "1_1") (pintype "passive"))
      (node (ref "SW1") (pin "2") (pinfunction "2_2") (pintype "passive"))
      (node (ref "SW2") (pin "1") (pinfunction "1_1") (pintype "passive"))
      (node (ref "SW2") (pin "2") (pinfunction "2_2") (pintype "passive"))
      (node (ref "SW3") (pin "1") (pinfunction "1_1") (pintype "passive"))
      (node (ref "SW3") (pin "2") (pinfunction "2_2") (pintype "passive"))
      (node (ref "U1") (pin "0") (pinfunction "EPAD_0") (pintype "passive"))
      (node (ref "U1") (pin "100") (pinfunction "GNDREG_100") (pintype "passive"))
      (node (ref "U1") (pin "16") (pinfunction "GNDIOK_16") (pintype "passive"))
      (node (ref "U1") (pin "36") (pinfunction "GNDIOK_36") (pintype "passive"))
      (node (ref "U1") (pin "48") (pinfunction "GNDXT_48") (pintype "passive"))
      (node (ref "U1") (pin "51") (pinfunction "GNDPLL_51") (pintype "passive"))
      (node (ref "U1") (pin "6") (pinfunction "GNDADC_6") (pintype "passive"))
      (node (ref "U1") (pin "68") (pinfunction "GNDIOK_68") (pintype "passive"))
      (node (ref "U1") (pin "80") (pinfunction "GNDIO_80") (pintype "passive"))
      (node (ref "U1") (pin "9") (pinfunction "GND18ADC_9") (pintype "passive"))
      (node (ref "U1") (pin "94") (pinfunction "GNDLP_94") (pintype "passive"))
      (node (ref "U2") (pin "15") (pinfunction "VSS_15") (pintype "passive"))
      (node (ref "U3") (pin "4") (pinfunction "GND_4") (pintype "passive"))
      (node (ref "U4") (pin "2") (pinfunction "GND_2") (pintype "passive"))
    )
    (net (code "67") (name "Net-(C25-Pad1)") (class "Default")
      (node (ref "C25") (pin "1") (pinfunction "1_1") (pintype "passive"))
      (node (ref "R21") (pin "2") (pinfunction "2_2") (pintype "passive"))
      (node (ref "R22") (pin "1") (pinfunction "1_1") (pintype "passive"))
    )
    (net (code "68") (name "Net-(C26-Pad1)") (class "Default")
      (node (ref "C26") (pin "1") (pinfunction "1_1") (pintype "passive"))
      (node (ref "R22") (pin "2") (pinfunction "2_2") (pintype "passive"))
      (node (ref "R23") (pin "1") (pinfunction "1_1") (pintype "passive"))
    )
    (net (code "69") (name "Net-(D4-Pad2)") (class "Default")
      (node (ref "D4") (pin "2") (pinfunction "2_2") (pintype "passive"))
      (node (ref "H6") (pin "8") (pinfunction "8_8") (pintype "passive"))
    )
    (net (code "70") (name "Net-(D5-Pad2)") (class "Default")
      (node (ref "D5") (pin "2") (pinfunction "2_2") (pintype "passive"))
      (node (ref "SW3") (pin "3") (pinfunction "3_3") (pintype "passive"))
      (node (ref "SW3") (pin "4") (pinfunction "4_4") (pintype "passive"))
    )
    (net (code "71") (name "Net-(D6-Pad2)") (class "Default")
      (node (ref "D6") (pin "2") (pinfunction "2_2") (pintype "passive"))
      (node (ref "H2") (pin "1") (pinfunction "1_1") (pintype "passive"))
    )
    (net (code "72") (name "Net-(F1-Pad1)") (class "Default")
      (node (ref "F1") (pin "1") (pinfunction "1_1") (pintype "passive"))
      (node (ref "J1") (pin "A4") (pinfunction "VBUS_A4") (pintype "passive"))
      (node (ref "J1") (pin "A9") (pinfunction "VBUS_A9") (pintype "passive"))
      (node (ref "J1") (pin "B4") (pinfunction "VBUS_B4") (pintype "passive"))
      (node (ref "J1") (pin "B9") (pinfunction "VBUS_B9") (pintype "passive"))
    )
    (net (code "73") (name "Net-(H3-RST)") (class "Default")
      (node (ref "D2") (pin "2") (pinfunction "2_2") (pintype "passive"))
      (node (ref "H3") (pin "8") (pinfunction "RST_8") (pintype "passive"))
    )
    (net (code "74") (name "Net-(J1-CC1)") (class "Default")
      (node (ref "J1") (pin "A5") (pinfunction "CC1_A5") (pintype "passive"))
      (node (ref "R5") (pin "2") (pinfunction "2_2") (pintype "passive"))
    )
    (net (code "75") (name "Net-(J1-CC2)") (class "Default")
      (node (ref "J1") (pin "B5") (pinfunction "CC2_B5") (pintype "passive"))
      (node (ref "R4") (pin "2") (pinfunction "2_2") (pintype "passive"))
    )
    (net (code "76") (name "Net-(J1-Shell)") (class "Default")
      (node (ref "J1") (pin "0") (pinfunction "Shell_0") (pintype "passive"))
      (node (ref "R18") (pin "2") (pinfunction "2_2") (pintype "passive"))
    )
    (net (code "77") (name "Net-(LED1-Pad1)") (class "Default")
      (node (ref "LED1") (pin "1") (pinfunction "1_1") (pintype "passive"))
      (node (ref "R6") (pin "1") (pinfunction "1_1") (pintype "passive"))
    )
    (net (code "78") (name "Net-(LED1-Pad2)") (class "Default")
      (node (ref "LED1") (pin "2") (pinfunction "2_2") (pintype "passive"))
      (node (ref "R7") (pin "1") (pinfunction "1_1") (pintype "passive"))
    )
    (net (code "79") (name "Net-(LED1-Pad3)") (class "Default")
      (node (ref "LED1") (pin "3") (pinfunction "3_3") (pintype "passive"))
      (node (ref "R8") (pin "2") (pinfunction "2_2") (pintype "passive"))
    )
    (net (code "80") (name "Net-(LED2-Pad1)") (class "Default")
      (node (ref "LED2") (pin "1") (pinfunction "1_1") (pintype "passive"))
      (node (ref "R15") (pin "2") (pinfunction "2_2") (pintype "passive"))
    )
    (net (code "81") (name "Net-(LED3-Pad1)") (class "Default")
      (node (ref "LED3") (pin "1") (pinfunction "1_1") (pintype "passive"))
      (node (ref "R16") (pin "2") (pinfunction "2_2") (pintype "passive"))
    )
    (net (code "82") (name "Net-(LED4-Pad1)") (class "Default")
      (node (ref "LED4") (pin "1") (pinfunction "1_1") (pintype "passive"))
      (node (ref "R17") (pin "1") (pinfunction "1_1") (pintype "passive"))
    )
    (net (code "83") (name "Net-(Q1-PadB)") (class "Default")
      (node (ref "Q1") (pin "B") (pinfunction "B_B") (pintype "passive"))
      (node (ref "R9") (pin "2") (pinfunction "2_2") (pintype "passive"))
    )
    (net (code "84") (name "Net-(Q1-PadC)") (class "Default")
      (node (ref "Q1") (pin "C") (pinfunction "C_C") (pintype "passive"))
      (node (ref "R6") (pin "2") (pinfunction "2_2") (pintype "passive"))
    )
    (net (code "85") (name "Net-(Q2-PadB)") (class "Default")
      (node (ref "Q2") (pin "B") (pinfunction "B_B") (pintype "passive"))
      (node (ref "R11") (pin "2") (pinfunction "2_2") (pintype "passive"))
    )
    (net (code "86") (name "Net-(Q2-PadC)") (class "Default")
      (node (ref "Q2") (pin "C") (pinfunction "C_C") (pintype "passive"))
      (node (ref "R7") (pin "2") (pinfunction "2_2") (pintype "passive"))
    )
    (net (code "87") (name "Net-(Q3-PadB)") (class "Default")
      (node (ref "Q3") (pin "B") (pinfunction "B_B") (pintype "passive"))
      (node (ref "R12") (pin "2") (pinfunction "2_2") (pintype "passive"))
    )
    (net (code "88") (name "Net-(Q3-PadC)") (class "Default")
      (node (ref "Q3") (pin "C") (pinfunction "C_C") (pintype "passive"))
      (node (ref "R8") (pin "1") (pinfunction "1_1") (pintype "passive"))
    )
    (net (code "89") (name "Net-(R10-Pad2)") (class "Default")
      (node (ref "R10") (pin "2") (pinfunction "2_2") (pintype "passive"))
      (node (ref "SW1") (pin "3") (pinfunction "3_3") (pintype "passive"))
      (node (ref "SW1") (pin "4") (pinfunction "4_4") (pintype "passive"))
    )
    (net (code "90") (name "Net-(R13-Pad2)") (class "Default")
      (node (ref "R13") (pin "2") (pinfunction "2_2") (pintype "passive"))
      (node (ref "SW2") (pin "3") (pinfunction "3_3") (pintype "passive"))
      (node (ref "SW2") (pin "4") (pinfunction "4_4") (pintype "passive"))
    )
    (net (code "91") (name "Net-(U1-RCI)") (class "Default")
      (node (ref "C18") (pin "2") (pinfunction "2_2") (pintype "passive"))
      (node (ref "R3") (pin "2") (pinfunction "2_2") (pintype "passive"))
      (node (ref "U1") (pin "93") (pinfunction "RCI_93") (pintype "passive"))
    )
    (net (code "92") (name "Net-(U1-RCO)") (class "Default")
      (node (ref "R3") (pin "1") (pinfunction "1_1") (pintype "passive"))
      (node (ref "U1") (pin "92") (pinfunction "RCO_92") (pintype "passive"))
    )
    (net (code "93") (name "Net-(U1-REGEN)") (class "Default")
      (node (ref "R2") (pin "1") (pinfunction "1_1") (pintype "passive"))
      (node (ref "U1") (pin "97") (pinfunction "REGEN_97") (pintype "passive"))
    )
    (net (code "94") (name "Net-(U1-VDC)") (class "Default")
      (node (ref "C24") (pin "2") (pinfunction "2_2") (pintype "passive"))
      (node (ref "R21") (pin "1") (pinfunction "1_1") (pintype "passive"))
      (node (ref "U1") (pin "49") (pinfunction "VDC_49") (pintype "passive"))
    )
    (net (code "95") (name "Net-(U1-XTI)") (class "Default")
      (node (ref "C1") (pin "1") (pinfunction "1_1") (pintype "passive"))
      (node (ref "U1") (pin "46") (pinfunction "XTI_46") (pintype "passive"))
      (node (ref "X1") (pin "1") (pinfunction "1_1") (pintype "passive"))
    )
    (net (code "96") (name "Net-(U1-XTO)") (class "Default")
      (node (ref "C2") (pin "1") (pinfunction "1_1") (pintype "passive"))
      (node (ref "C24") (pin "1") (pinfunction "1_1") (pintype "passive"))
      (node (ref "U1") (pin "47") (pinfunction "XTO_47") (pintype "passive"))
      (node (ref "X1") (pin "2") (pinfunction "2_2") (pintype "passive"))
    )
    (net (code "97") (name "Net-(U2-NRST)") (class "Default")
      (node (ref "C21") (pin "1") (pinfunction "1_1") (pintype "passive"))
      (node (ref "U2") (pin "4") (pinfunction "NRST_4") (pintype "passive"))
    )
    (net (code "98") (name "Net-(U2-PA0)") (class "Default")
      (node (ref "D3") (pin "2") (pinfunction "2_2") (pintype "passive"))
      (node (ref "U2") (pin "6") (pinfunction "PA0_6") (pintype "passive"))
    )
    (net (code "99") (name "Net-(U2-PB1)") (class "Default")
      (node (ref "R15") (pin "1") (pinfunction "1_1") (pintype "passive"))
      (node (ref "U2") (pin "14") (pinfunction "PB1_14") (pintype "passive"))
    )
    (net (code "100") (name "Net-(U2-PB8-BOOT0)") (class "Default")
      (node (ref "H4") (pin "1") (pinfunction "1_1") (pintype "passive"))
      (node (ref "R14") (pin "2") (pinfunction "2_2") (pintype "passive"))
      (node (ref "U2") (pin "1") (pinfunction "PB8-BOOT0_1") (pintype "passive"))
    )
    (net (code "101") (name "Net-(U2-PF0)") (class "Default")
      (node (ref "R16") (pin "1") (pinfunction "1_1") (pintype "passive"))
      (node (ref "U2") (pin "2") (pinfunction "PF0_2") (pintype "passive"))
    )
    (net (code "102") (name "Net-(U2-PF1)") (class "Default")
      (node (ref "R17") (pin "2") (pinfunction "2_2") (pintype "passive"))
      (node (ref "U2") (pin "3") (pinfunction "PF1_3") (pintype "passive"))
    )
    (net (code "103") (name "VBUS") (class "Default")
      (node (ref "C3") (pin "1") (pinfunction "1_1") (pintype "passive"))
      (node (ref "C4") (pin "1") (pinfunction "1_1") (pintype "passive"))
      (node (ref "D1") (pin "5") (pinfunction "5_5") (pintype "passive"))
      (node (ref "F1") (pin "2") (pinfunction "2_2") (pintype "passive"))
      (node (ref "L1") (pin "1") (pinfunction "1_1") (pintype "passive"))
    )
    (net (code "104") (name "unconnected-(J1-SBU1-PadA8)") (class "Default")
      (node (ref "J1") (pin "A8") (pinfunction "SBU1_A8") (pintype "passive+no_connect"))
    )
    (net (code "105") (name "unconnected-(J1-SBU2-PadB8)") (class "Default")
      (node (ref "J1") (pin "B8") (pinfunction "SBU2_B8") (pintype "passive+no_connect"))
    )
    (net (code "106") (name "unconnected-(U1-LPPD-Pad96)") (class "Default")
      (node (ref "U1") (pin "96") (pinfunction "LPPD_96") (pintype "output+no_connect"))
    )
    (net (code "107") (name "unconnected-(U1-PB2-Pad39)") (class "Default")
      (node (ref "U1") (pin "39") (pinfunction "PB2_39") (pintype "passive+no_connect"))
    )
    (net (code "108") (name "unconnected-(U1-PG3{slash}SEN0-Pad33)") (class "Default")
      (node (ref "U1") (pin "33") (pinfunction "PG3/SEN0_33") (pintype "passive+no_connect"))
    )
    (net (code "109") (name "unconnected-(U1-PORDIS-Pad89)") (class "Default")
      (node (ref "U1") (pin "89") (pinfunction "PORDIS_89") (pintype "passive+no_connect"))
    )
    (net (code "110") (name "unconnected-(U1-PORRES-Pad90)") (class "Default")
      (node (ref "U1") (pin "90") (pinfunction "PORRES_90") (pintype "passive+no_connect"))
    )
    (net (code "111") (name "unconnected-(U1-TESTP_IP-Pad77)") (class "Default")
      (node (ref "U1") (pin "77") (pinfunction "TESTP_IP_77") (pintype "passive+no_connect"))
    )
    (net (code "112") (name "unconnected-(U1-TEST_M-Pad78)") (class "Default")
      (node (ref "U1") (pin "78") (pinfunction "TEST_M_78") (pintype "passive+no_connect"))
    )
    (net (code "113") (name "unconnected-(U1-mbist_PS_sel-Pad27)") (class "Default")
      (node (ref "U1") (pin "27") (pinfunction "mbist_PS_sel_27") (pintype "passive+no_connect"))
    )
    (net (code "114") (name "unconnected-(U1-mbist_hold_1-Pad28)") (class "Default")
      (node (ref "U1") (pin "28") (pinfunction "mbist_hold_1_28") (pintype "passive+no_connect"))
    )
    (net (code "115") (name "unconnected-(U1-scan_en-Pad75)") (class "Default")
      (node (ref "U1") (pin "75") (pinfunction "scan_en_75") (pintype "passive+no_connect"))
    )
    (net (code "116") (name "unconnected-(U1-scan_test-Pad76)") (class "Default")
      (node (ref "U1") (pin "76") (pinfunction "scan_test_76") (pintype "passive+no_connect"))
    )
    (net (code "117") (name "unconnected-(U2-PA3-Pad9)") (class "Default")
      (node (ref "U2") (pin "9") (pinfunction "PA3_9") (pintype "passive+no_connect"))
    )
  )
)
